# ngoc_say.net
KiCad netlist of a schematic drawn in Altium Designer
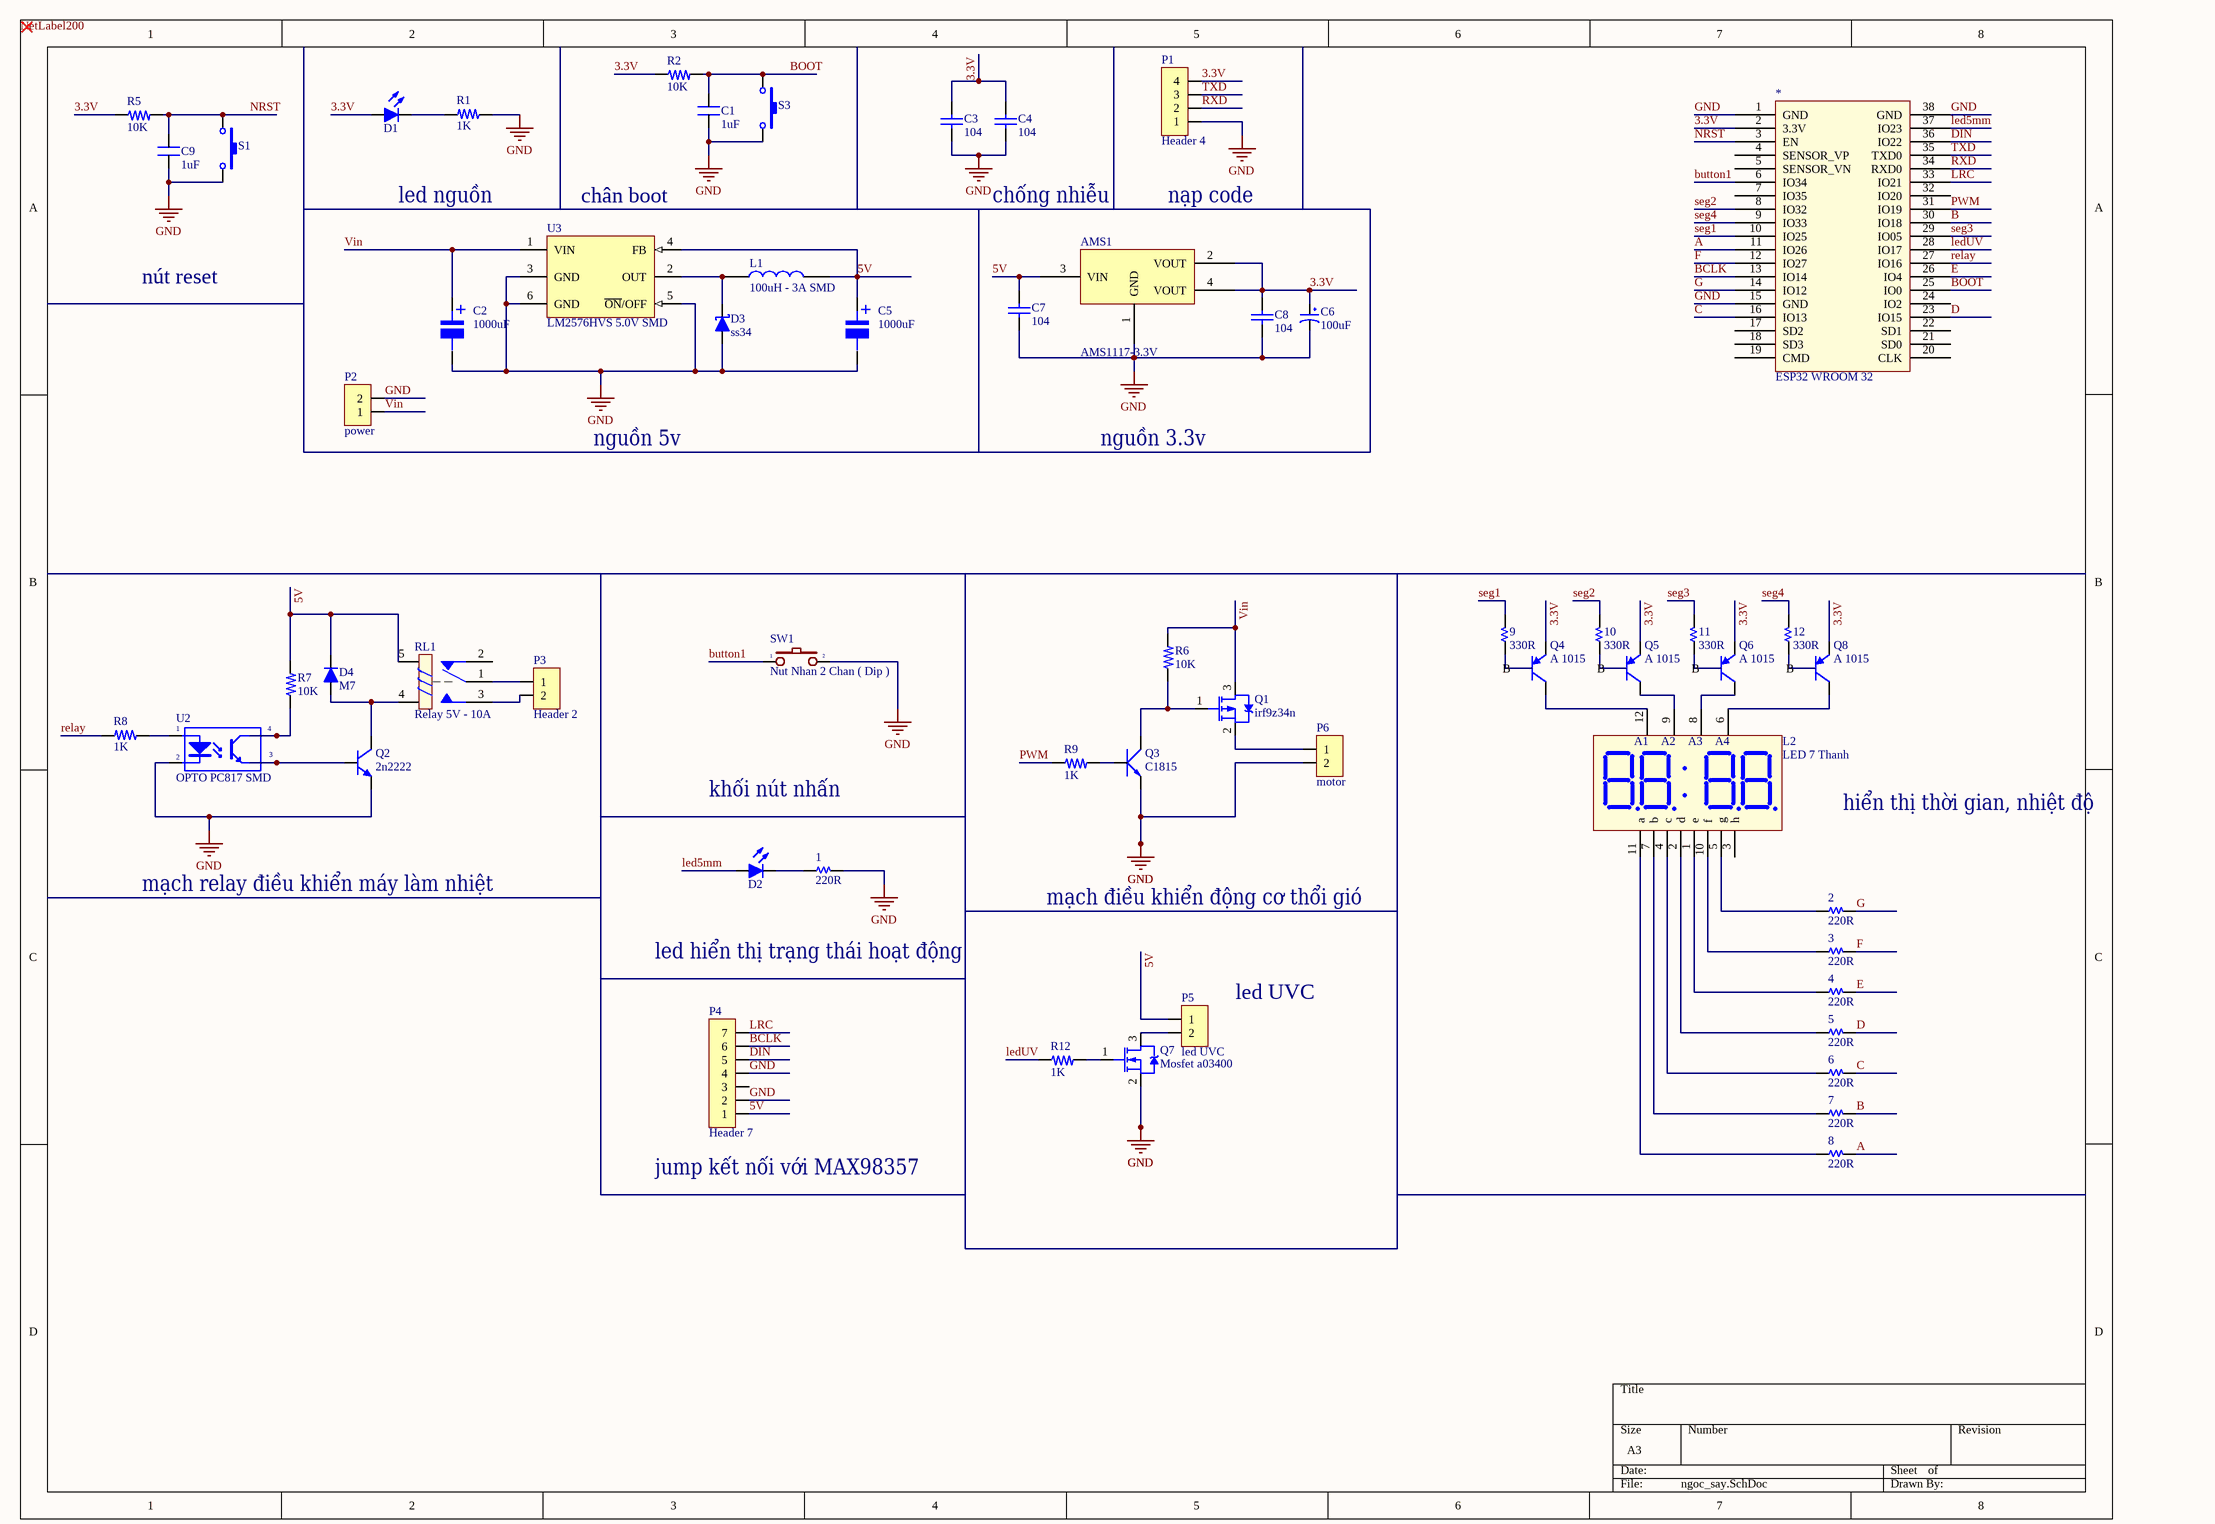
[diagram p0: ngoc_say.SchDoc]

(export (version "E")
  (design (tool "Eeschema 10.0.6"))
  (components
    (comp (ref "*")
      (value "ESP32 WROOM 32")
      (footprint "ESP32-WROOM-32")
      (libsource (lib "IC") (part "ESP32 WROOM 32"))
    )
    (comp (ref "1")
      (value "220R")
      (footprint "R 0805")
      (description "Resistor")
      (libsource (lib "chipfc_libs") (part "Resistor"))
    )
    (comp (ref "2")
      (value "220R")
      (footprint "R 0805")
      (description "Resistor")
      (libsource (lib "chipfc_libs") (part "Resistor"))
    )
    (comp (ref "3")
      (value "220R")
      (footprint "R 0805")
      (description "Resistor")
      (libsource (lib "chipfc_libs") (part "Resistor"))
    )
    (comp (ref "4")
      (value "220R")
      (footprint "R 0805")
      (description "Resistor")
      (libsource (lib "chipfc_libs") (part "Resistor"))
    )
    (comp (ref "5")
      (value "220R")
      (footprint "R 0805")
      (description "Resistor")
      (libsource (lib "chipfc_libs") (part "Resistor"))
    )
    (comp (ref "6")
      (value "220R")
      (footprint "R 0805")
      (description "Resistor")
      (libsource (lib "chipfc_libs") (part "Resistor"))
    )
    (comp (ref "7")
      (value "220R")
      (footprint "R 0805")
      (description "Resistor")
      (libsource (lib "chipfc_libs") (part "Resistor"))
    )
    (comp (ref "8")
      (value "220R")
      (footprint "R 0805")
      (description "Resistor")
      (libsource (lib "chipfc_libs") (part "Resistor"))
    )
    (comp (ref "9")
      (value "330R")
      (footprint "R 0805")
      (description "Resistor")
      (libsource (lib "chipfc_libs") (part "Resistor"))
    )
    (comp (ref "10")
      (value "330R")
      (footprint "R 0805")
      (description "Resistor")
      (libsource (lib "chipfc_libs") (part "Resistor"))
    )
    (comp (ref "11")
      (value "330R")
      (footprint "R 0805")
      (description "Resistor")
      (libsource (lib "chipfc_libs") (part "Resistor"))
    )
    (comp (ref "12")
      (value "330R")
      (footprint "R 0805")
      (description "Resistor")
      (libsource (lib "chipfc_libs") (part "Resistor"))
    )
    (comp (ref "AMS1")
      (value "AMS1117-3.3V")
      (footprint "SOT223")
      (description "Dán")
      (libsource (lib "IC") (part "AMS1117 SMD"))
    )
    (comp (ref "C1")
      (value "1uF")
      (footprint "CAP_0805")
      (description "1µF ±5% 50V Ceramic Capacitor X7R 0805 (2012 Metric)")
      (fields
        (field (name "MANUFACTURER") "Yageo")
        (field (name "MANUFACTURING PART NUMBER") "CC0805JKX7R9BB105")
      )
      (libsource (lib "STM_SCH_LIB") (part "CAP_1uF-50V-5%-0805"))
    )
    (comp (ref "C2")
      (value "1000uF")
      (footprint "tu nhom 10 (G)")
      (description "Dán")
      (libsource (lib "THU VIEN SCH") (part "Tu Nhom 1000uF 16V"))
    )
    (comp (ref "C3")
      (value "104")
      (footprint "Tu 0805")
      (description "Dán")
      (libsource (lib "THU VIEN SCH") (part "Tu 104"))
    )
    (comp (ref "C4")
      (value "104")
      (footprint "Tu 0805")
      (description "Dán")
      (libsource (lib "THU VIEN SCH") (part "Tu 104"))
    )
    (comp (ref "C5")
      (value "1000uF")
      (footprint "tu nhom 10 (G)")
      (description "Dán")
      (libsource (lib "THU VIEN SCH") (part "Tu Nhom 1000uF 16V"))
    )
    (comp (ref "C6")
      (value "100uF")
      (footprint "tu tantalum smd3528")
      (description "Dán")
      (libsource (lib "THU VIEN SCH") (part "Tu tantalum 100uF 6.3V SMD3528"))
    )
    (comp (ref "C7")
      (value "104")
      (footprint "Tu 0805")
      (description "Dán")
      (libsource (lib "THU VIEN SCH") (part "Tu 104"))
    )
    (comp (ref "C8")
      (value "104")
      (footprint "Tu 0805")
      (description "Dán")
      (libsource (lib "THU VIEN SCH") (part "Tu 104"))
    )
    (comp (ref "C9")
      (value "1uF")
      (footprint "CAP_0805")
      (description "1µF ±5% 50V Ceramic Capacitor X7R 0805 (2012 Metric)")
      (fields
        (field (name "MANUFACTURER") "Yageo")
        (field (name "MANUFACTURING PART NUMBER") "CC0805JKX7R9BB105")
      )
      (libsource (lib "STM_SCH_LIB") (part "CAP_1uF-50V-5%-0805"))
    )
    (comp (ref "D1")
      (value "Led")
      (footprint "Led 0805 RED")
      (description "Typical LED")
      (libsource (lib "led") (part "Led"))
    )
    (comp (ref "D2")
      (value "Led")
      (footprint "LED 5MM - RED")
      (description "Typical LED")
      (libsource (lib "led") (part "Led"))
    )
    (comp (ref "D3")
      (value "ss34")
      (footprint "SOD123")
      (description "Schottky Diode")
      (libsource (lib "chipfc_libs") (part "Diode Schottky"))
    )
    (comp (ref "D4")
      (value "M7")
      (footprint "DO-214AC (SMA) L")
      (description "Default Diode")
      (libsource (lib "chipfc_libs") (part "Diode"))
    )
    (comp (ref "L1")
      (value "100uH - 3A SMD")
      (footprint "Cuon Cam 7.5x7x5")
      (description "Dán")
      (libsource (lib "THU VIEN SCH") (part "CUON CAM 100uH_SMD"))
    )
    (comp (ref "L2")
      (value "LED 7 Thanh")
      (footprint "LED 7x4 0.36")
      (description "Dán")
      (libsource (lib "Led") (part "LED 7x4 0.36 Anot"))
    )
    (comp (ref "P1")
      (value "Header 4")
      (footprint "HDR/Header/4/2mm")
      (description "Header, 4-Pin")
      (libsource (lib "connectors") (part "Header 4"))
    )
    (comp (ref "P2")
      (value "power")
      (footprint "HDR/Header/2/BOX")
      (description "Header, 2-Pin")
      (libsource (lib "connectors") (part "Header 2"))
    )
    (comp (ref "P3")
      (value "Header 2")
      (footprint "HDR/Terminal/2")
      (description "Header, 2-Pin")
      (libsource (lib "") (part "Header 2_1"))
    )
    (comp (ref "P4")
      (value "Header 7")
      (footprint "HDR/Header/7/2mm")
      (description "Header, 7-Pin")
      (libsource (lib "connectors") (part "Header 7"))
    )
    (comp (ref "P5")
      (value "led UVC")
      (footprint "HDR/Header/2/BOX")
      (description "Header, 2-Pin")
      (libsource (lib "") (part "Header 2_1"))
    )
    (comp (ref "P6")
      (value "motor")
      (footprint "HDR/Header/2/BOX")
      (description "Header, 2-Pin")
      (libsource (lib "") (part "Header 2_1"))
    )
    (comp (ref "Q1")
      (value "irf9z34n")
      (footprint "TO-220/HeatSink")
      (description "Mosfet P")
      (libsource (lib "chipfc_libs") (part "Mosfet P"))
    )
    (comp (ref "Q2")
      (value "2n2222")
      (footprint "SOT-23")
      (description "NPN Bipolar Transistor")
      (libsource (lib "chipfc_libs") (part "Transistor NPN"))
    )
    (comp (ref "Q3")
      (value "C1815")
      (footprint "SOT23B")
      (description "Dán")
      (libsource (lib "THU VIEN SCH") (part "C1815"))
    )
    (comp (ref "Q4")
      (value "A 1015")
      (footprint "SOT23")
      (description "Dán")
      (libsource (lib "THU VIEN SCH") (part "2SA1015"))
    )
    (comp (ref "Q5")
      (value "A 1015")
      (footprint "SOT23")
      (description "Dán")
      (libsource (lib "THU VIEN SCH") (part "2SA1015"))
    )
    (comp (ref "Q6")
      (value "A 1015")
      (footprint "SOT23")
      (description "Dán")
      (libsource (lib "THU VIEN SCH") (part "2SA1015"))
    )
    (comp (ref "Q7")
      (value "Mosfet a03400")
      (footprint "SOT-23")
      (description "Mosfet N")
      (libsource (lib "chipfc_libs") (part "Mosfet N"))
    )
    (comp (ref "Q8")
      (value "A 1015")
      (footprint "SOT23")
      (description "Dán")
      (libsource (lib "THU VIEN SCH") (part "2SA1015"))
    )
    (comp (ref "R1")
      (value "1K")
      (footprint "RES_0805")
      (description "1 kOhms ±1% 0.125W, 1/8W Chip Resistor 0805 (2012 Metric) Moisture Resistant Thick Film")
      (fields (field (name "MANUFACTURER") "垈㎵á") (field (name "MANUFACTURER PART NUMBER") "RC0805FR-071KL"))
      (libsource (lib "STM_SCH_LIB") (part "RES_1K-0.125W-1%-0805"))
    )
    (comp (ref "R2")
      (value "10K")
      (footprint "RES_0805")
      (description "10 kOhms ±1% 0.125W, 1/8W Chip Resistor 0805 (2012 Metric) Moisture Resistant Thick Film")
      (fields
        (field (name "MANUFACTURER") "Yageo")
        (field (name "MANUFACTURING PART NUMBER") "RC0805FR-0710KL")
      )
      (libsource (lib "STM_SCH_LIB") (part "RES_10K-0.125W-1%-0805"))
    )
    (comp (ref "R5")
      (value "10K")
      (footprint "RES_0805")
      (description "10 kOhms ±1% 0.125W, 1/8W Chip Resistor 0805 (2012 Metric) Moisture Resistant Thick Film")
      (fields
        (field (name "MANUFACTURER") "Yageo")
        (field (name "MANUFACTURING PART NUMBER") "RC0805FR-0710KL")
      )
      (libsource (lib "STM_SCH_LIB") (part "RES_10K-0.125W-1%-0805"))
    )
    (comp (ref "R6")
      (value "10K")
      (footprint "RES_0805")
      (description "10 kOhms ±1% 0.125W, 1/8W Chip Resistor 0805 (2012 Metric) Moisture Resistant Thick Film")
      (fields
        (field (name "MANUFACTURER") "Yageo")
        (field (name "MANUFACTURING PART NUMBER") "RC0805FR-0710KL")
      )
      (libsource (lib "STM_SCH_LIB") (part "RES_10K-0.125W-1%-0805"))
    )
    (comp (ref "R7")
      (value "10K")
      (footprint "RES_0805")
      (description "10 kOhms ±1% 0.125W, 1/8W Chip Resistor 0805 (2012 Metric) Moisture Resistant Thick Film")
      (fields
        (field (name "MANUFACTURER") "Yageo")
        (field (name "MANUFACTURING PART NUMBER") "RC0805FR-0710KL")
      )
      (libsource (lib "STM_SCH_LIB") (part "RES_10K-0.125W-1%-0805"))
    )
    (comp (ref "R8")
      (value "1K")
      (footprint "RES_0805")
      (description "1 kOhms ±1% 0.125W, 1/8W Chip Resistor 0805 (2012 Metric) Moisture Resistant Thick Film")
      (fields (field (name "MANUFACTURER") "垈㎵á") (field (name "MANUFACTURER PART NUMBER") "RC0805FR-071KL"))
      (libsource (lib "STM_SCH_LIB") (part "RES_1K-0.125W-1%-0805"))
    )
    (comp (ref "R9")
      (value "1K")
      (footprint "RES_0805")
      (description "1 kOhms ±1% 0.125W, 1/8W Chip Resistor 0805 (2012 Metric) Moisture Resistant Thick Film")
      (fields (field (name "MANUFACTURER") "垈㎵á") (field (name "MANUFACTURER PART NUMBER") "RC0805FR-071KL"))
      (libsource (lib "STM_SCH_LIB") (part "RES_1K-0.125W-1%-0805"))
    )
    (comp (ref "R12")
      (value "1K")
      (footprint "RES_0805")
      (description "1 kOhms ±1% 0.125W, 1/8W Chip Resistor 0805 (2012 Metric) Moisture Resistant Thick Film")
      (fields (field (name "MANUFACTURER") "垈㎵á") (field (name "MANUFACTURER PART NUMBER") "RC0805FR-071KL"))
      (libsource (lib "STM_SCH_LIB") (part "RES_1K-0.125W-1%-0805"))
    )
    (comp (ref "RL1")
      (value "Relay 5V - 10A")
      (footprint "RELAY5PIN-10A")
      (description "Cắm")
      (fields (field (name "Comment") "MH"))
      (libsource (lib "THU VIEN SCH") (part "Relay 10A"))
    )
    (comp (ref "S1")
      (value "MH001036")
      (footprint "SW-SMD")
      (description "Dán")
      (libsource (lib "THU VIEN SCH") (part "SW-SMD"))
    )
    (comp (ref "S3")
      (value "MH001036")
      (footprint "SW-SMD")
      (description "Dán")
      (libsource (lib "THU VIEN SCH") (part "SW-SMD"))
    )
    (comp (ref "SW1")
      (value "Nut Nhan 2 Chan ( Dip )")
      (footprint "SW2")
      (description "Cắm")
      (libsource (lib "THU VIEN SCH") (part "Nut Nhan 2 Chan ( Dip )"))
    )
    (comp (ref "U2")
      (value "OPTO PC817 SMD")
      (footprint "SOP4")
      (description "Single Opto")
      (libsource (lib "IC") (part "OPTO PC817 SMD"))
    )
    (comp (ref "U3")
      (value "LM2576HVS 5.0V SMD")
      (footprint "TO263-5")
      (description "Dán")
      (libsource (lib "IC") (part "LM2576HVS 5.0V SMD"))
    )
  )
  (nets
    (net (code "1") (name "/3.3V") (class "Default")
      (node (ref "*") (pin "2") (pinfunction "3.3V_2") (pintype "passive"))
      (node (ref "AMS1") (pin "2") (pinfunction "VOUT_2") (pintype "passive"))
      (node (ref "AMS1") (pin "4") (pinfunction "VOUT_4") (pintype "passive"))
      (node (ref "C3") (pin "2") (pinfunction "2_2") (pintype "passive"))
      (node (ref "C4") (pin "2") (pinfunction "2_2") (pintype "passive"))
      (node (ref "C6") (pin "1") (pinfunction "1_1") (pintype "passive"))
      (node (ref "C8") (pin "2") (pinfunction "2_2") (pintype "passive"))
      (node (ref "D1") (pin "1") (pinfunction "A_1") (pintype "passive"))
      (node (ref "P1") (pin "4") (pinfunction "4_4") (pintype "passive"))
      (node (ref "Q4") (pin "3") (pinfunction "E_3") (pintype "passive"))
      (node (ref "Q5") (pin "3") (pinfunction "E_3") (pintype "passive"))
      (node (ref "Q6") (pin "3") (pinfunction "E_3") (pintype "passive"))
      (node (ref "Q8") (pin "3") (pinfunction "E_3") (pintype "passive"))
      (node (ref "R2") (pin "2") (pinfunction "2_2") (pintype "passive"))
      (node (ref "R5") (pin "2") (pinfunction "2_2") (pintype "passive"))
    )
    (net (code "2") (name "/5V") (class "Default")
      (node (ref "AMS1") (pin "3") (pinfunction "VIN_3") (pintype "passive"))
      (node (ref "C5") (pin "1") (pinfunction "1_1") (pintype "passive"))
      (node (ref "C7") (pin "2") (pinfunction "2_2") (pintype "passive"))
      (node (ref "D4") (pin "2") (pinfunction "K_2") (pintype "passive"))
      (node (ref "L1") (pin "2") (pinfunction "2_2") (pintype "passive"))
      (node (ref "P4") (pin "1") (pinfunction "1_1") (pintype "passive"))
      (node (ref "P5") (pin "1") (pinfunction "1_1") (pintype "passive"))
      (node (ref "R7") (pin "1") (pinfunction "1_1") (pintype "passive"))
      (node (ref "RL1") (pin "5") (pinfunction "5_5") (pintype "passive"))
      (node (ref "U3") (pin "4") (pinfunction "FB_4") (pintype "input"))
    )
    (net (code "3") (name "/A") (class "Default")
      (node (ref "*") (pin "11") (pinfunction "IO26_11") (pintype "passive"))
      (node (ref "8") (pin "2") (pinfunction "2_2") (pintype "passive"))
    )
    (net (code "4") (name "/B") (class "Default")
      (node (ref "*") (pin "30") (pinfunction "IO18_30") (pintype "passive"))
      (node (ref "7") (pin "2") (pinfunction "2_2") (pintype "passive"))
    )
    (net (code "5") (name "/BCLK") (class "Default")
      (node (ref "*") (pin "13") (pinfunction "IO14_13") (pintype "passive"))
      (node (ref "P4") (pin "6") (pinfunction "6_6") (pintype "passive"))
    )
    (net (code "6") (name "/BOOT") (class "Default")
      (node (ref "*") (pin "25") (pinfunction "IO0_25") (pintype "passive"))
      (node (ref "C1") (pin "2") (pinfunction "2_2") (pintype "passive"))
      (node (ref "R2") (pin "1") (pinfunction "1_1") (pintype "passive"))
      (node (ref "S3") (pin "1") (pinfunction "1_1") (pintype "passive"))
    )
    (net (code "7") (name "/C") (class "Default")
      (node (ref "*") (pin "16") (pinfunction "IO13_16") (pintype "passive"))
      (node (ref "6") (pin "2") (pinfunction "2_2") (pintype "passive"))
    )
    (net (code "8") (name "/D") (class "Default")
      (node (ref "*") (pin "23") (pinfunction "IO15_23") (pintype "passive"))
      (node (ref "5") (pin "2") (pinfunction "2_2") (pintype "passive"))
    )
    (net (code "9") (name "/DIN") (class "Default")
      (node (ref "*") (pin "36") (pinfunction "IO22_36") (pintype "passive"))
      (node (ref "P4") (pin "5") (pinfunction "5_5") (pintype "passive"))
    )
    (net (code "10") (name "/E") (class "Default")
      (node (ref "*") (pin "26") (pinfunction "IO4_26") (pintype "passive"))
      (node (ref "4") (pin "2") (pinfunction "2_2") (pintype "passive"))
    )
    (net (code "11") (name "/F") (class "Default")
      (node (ref "*") (pin "12") (pinfunction "IO27_12") (pintype "passive"))
      (node (ref "3") (pin "2") (pinfunction "2_2") (pintype "passive"))
    )
    (net (code "12") (name "/G") (class "Default")
      (node (ref "*") (pin "14") (pinfunction "IO12_14") (pintype "passive"))
      (node (ref "2") (pin "2") (pinfunction "2_2") (pintype "passive"))
    )
    (net (code "13") (name "/LRC") (class "Default")
      (node (ref "*") (pin "33") (pinfunction "IO21_33") (pintype "passive"))
      (node (ref "P4") (pin "7") (pinfunction "7_7") (pintype "passive"))
    )
    (net (code "14") (name "/NRST") (class "Default")
      (node (ref "*") (pin "3") (pinfunction "EN_3") (pintype "passive"))
      (node (ref "C9") (pin "2") (pinfunction "2_2") (pintype "passive"))
      (node (ref "R5") (pin "1") (pinfunction "1_1") (pintype "passive"))
      (node (ref "S1") (pin "1") (pinfunction "1_1") (pintype "passive"))
    )
    (net (code "16") (name "/PWM") (class "Default")
      (node (ref "*") (pin "31") (pinfunction "IO19_31") (pintype "passive"))
      (node (ref "R9") (pin "2") (pinfunction "2_2") (pintype "passive"))
    )
    (net (code "17") (name "/RXD") (class "Default")
      (node (ref "*") (pin "34") (pinfunction "RXD0_34") (pintype "passive"))
      (node (ref "P1") (pin "2") (pinfunction "2_2") (pintype "passive"))
    )
    (net (code "18") (name "/TXD") (class "Default")
      (node (ref "*") (pin "35") (pinfunction "TXD0_35") (pintype "passive"))
      (node (ref "P1") (pin "3") (pinfunction "3_3") (pintype "passive"))
    )
    (net (code "19") (name "/Vin") (class "Default")
      (node (ref "C2") (pin "1") (pinfunction "1_1") (pintype "passive"))
      (node (ref "P2") (pin "1") (pinfunction "1_1") (pintype "passive"))
      (node (ref "Q1") (pin "3") (pinfunction "D_3") (pintype "passive"))
      (node (ref "R6") (pin "1") (pinfunction "1_1") (pintype "passive"))
      (node (ref "U3") (pin "1") (pinfunction "VIN_1") (pintype "power_in"))
    )
    (net (code "20") (name "/button1") (class "Default")
      (node (ref "*") (pin "6") (pinfunction "IO34_6") (pintype "passive"))
      (node (ref "SW1") (pin "1") (pinfunction "1_1") (pintype "passive"))
    )
    (net (code "21") (name "/led5mm") (class "Default")
      (node (ref "*") (pin "37") (pinfunction "IO23_37") (pintype "passive"))
      (node (ref "D2") (pin "1") (pinfunction "A_1") (pintype "passive"))
    )
    (net (code "22") (name "/ledUV") (class "Default")
      (node (ref "*") (pin "28") (pinfunction "IO17_28") (pintype "passive"))
      (node (ref "R12") (pin "2") (pinfunction "2_2") (pintype "passive"))
    )
    (net (code "23") (name "/relay") (class "Default")
      (node (ref "*") (pin "27") (pinfunction "IO16_27") (pintype "passive"))
      (node (ref "R8") (pin "1") (pinfunction "1_1") (pintype "passive"))
    )
    (net (code "24") (name "/seg1") (class "Default")
      (node (ref "*") (pin "10") (pinfunction "IO25_10") (pintype "passive"))
      (node (ref "9") (pin "2") (pinfunction "2_2") (pintype "passive"))
    )
    (net (code "25") (name "/seg2") (class "Default")
      (node (ref "*") (pin "8") (pinfunction "IO32_8") (pintype "passive"))
      (node (ref "10") (pin "2") (pinfunction "2_2") (pintype "passive"))
    )
    (net (code "26") (name "/seg3") (class "Default")
      (node (ref "*") (pin "29") (pinfunction "IO05_29") (pintype "passive"))
      (node (ref "11") (pin "2") (pinfunction "2_2") (pintype "passive"))
    )
    (net (code "27") (name "/seg4") (class "Default")
      (node (ref "*") (pin "9") (pinfunction "IO33_9") (pintype "passive"))
      (node (ref "12") (pin "2") (pinfunction "2_2") (pintype "passive"))
    )
    (net (code "28") (name "GND") (class "Default")
      (node (ref "*") (pin "1") (pinfunction "GND_1") (pintype "passive"))
      (node (ref "*") (pin "15") (pinfunction "GND_15") (pintype "passive"))
      (node (ref "*") (pin "38") (pinfunction "GND_38") (pintype "passive"))
      (node (ref "1") (pin "2") (pinfunction "2_2") (pintype "passive"))
      (node (ref "AMS1") (pin "1") (pinfunction "GND_1") (pintype "passive"))
      (node (ref "C1") (pin "1") (pinfunction "1_1") (pintype "passive"))
      (node (ref "C2") (pin "2") (pinfunction "2_2") (pintype "passive"))
      (node (ref "C3") (pin "1") (pinfunction "1_1") (pintype "passive"))
      (node (ref "C4") (pin "1") (pinfunction "1_1") (pintype "passive"))
      (node (ref "C5") (pin "2") (pinfunction "2_2") (pintype "passive"))
      (node (ref "C6") (pin "2") (pinfunction "2_2") (pintype "passive"))
      (node (ref "C7") (pin "1") (pinfunction "1_1") (pintype "passive"))
      (node (ref "C8") (pin "1") (pinfunction "1_1") (pintype "passive"))
      (node (ref "C9") (pin "1") (pinfunction "1_1") (pintype "passive"))
      (node (ref "D3") (pin "1") (pinfunction "A_1") (pintype "passive"))
      (node (ref "P1") (pin "1") (pinfunction "1_1") (pintype "passive"))
      (node (ref "P2") (pin "2") (pinfunction "2_2") (pintype "passive"))
      (node (ref "P4") (pin "2") (pinfunction "2_2") (pintype "passive"))
      (node (ref "P4") (pin "4") (pinfunction "4_4") (pintype "passive"))
      (node (ref "P6") (pin "2") (pinfunction "2_2") (pintype "passive"))
      (node (ref "Q2") (pin "2") (pinfunction "E_2") (pintype "passive"))
      (node (ref "Q3") (pin "3") (pinfunction "E_3") (pintype "passive"))
      (node (ref "Q7") (pin "2") (pinfunction "S_2") (pintype "passive"))
      (node (ref "R1") (pin "2") (pinfunction "2_2") (pintype "passive"))
      (node (ref "S1") (pin "2") (pinfunction "2_2") (pintype "passive"))
      (node (ref "S3") (pin "2") (pinfunction "2_2") (pintype "passive"))
      (node (ref "SW1") (pin "2") (pinfunction "2_2") (pintype "passive"))
      (node (ref "U2") (pin "2") (pinfunction "K_2") (pintype "passive"))
      (node (ref "U3") (pin "3") (pinfunction "GND_3") (pintype "power_in"))
      (node (ref "U3") (pin "5") (pinfunction "~{ON}/OFF_5") (pintype "input"))
      (node (ref "U3") (pin "6") (pinfunction "GND_6") (pintype "passive"))
    )
    (net (code "29") (name "Net-(D1-K)") (class "Default")
      (node (ref "D1") (pin "2") (pinfunction "K_2") (pintype "passive"))
      (node (ref "R1") (pin "1") (pinfunction "1_1") (pintype "passive"))
    )
    (net (code "30") (name "Net-(D2-K)") (class "Default")
      (node (ref "1") (pin "1") (pinfunction "1_1") (pintype "passive"))
      (node (ref "D2") (pin "2") (pinfunction "K_2") (pintype "passive"))
    )
    (net (code "31") (name "Net-(D3-K)") (class "Default")
      (node (ref "D3") (pin "2") (pinfunction "K_2") (pintype "passive"))
      (node (ref "L1") (pin "1") (pinfunction "1_1") (pintype "passive"))
      (node (ref "U3") (pin "2") (pinfunction "OUT_2") (pintype "power_in"))
    )
    (net (code "32") (name "Net-(D4-A)") (class "Default")
      (node (ref "D4") (pin "1") (pinfunction "A_1") (pintype "passive"))
      (node (ref "Q2") (pin "3") (pinfunction "C_3") (pintype "passive"))
      (node (ref "RL1") (pin "4") (pinfunction "4_4") (pintype "passive"))
    )
    (net (code "33") (name "Net-(L2-V1)") (class "Default")
      (node (ref "L2") (pin "12") (pinfunction "V1_12") (pintype "passive"))
      (node (ref "Q4") (pin "2") (pinfunction "C_2") (pintype "passive"))
    )
    (net (code "34") (name "Net-(L2-V2)") (class "Default")
      (node (ref "L2") (pin "9") (pinfunction "V2_9") (pintype "passive"))
      (node (ref "Q5") (pin "2") (pinfunction "C_2") (pintype "passive"))
    )
    (net (code "35") (name "Net-(L2-V3)") (class "Default")
      (node (ref "L2") (pin "8") (pinfunction "V3_8") (pintype "passive"))
      (node (ref "Q6") (pin "2") (pinfunction "C_2") (pintype "passive"))
    )
    (net (code "36") (name "Net-(L2-V4)") (class "Default")
      (node (ref "L2") (pin "6") (pinfunction "V4_6") (pintype "passive"))
      (node (ref "Q8") (pin "2") (pinfunction "C_2") (pintype "passive"))
    )
    (net (code "37") (name "Net-(L2-a)") (class "Default")
      (node (ref "8") (pin "1") (pinfunction "1_1") (pintype "passive"))
      (node (ref "L2") (pin "11") (pinfunction "a_11") (pintype "passive"))
    )
    (net (code "38") (name "Net-(L2-b)") (class "Default")
      (node (ref "7") (pin "1") (pinfunction "1_1") (pintype "passive"))
      (node (ref "L2") (pin "7") (pinfunction "b_7") (pintype "passive"))
    )
    (net (code "39") (name "Net-(L2-c)") (class "Default")
      (node (ref "6") (pin "1") (pinfunction "1_1") (pintype "passive"))
      (node (ref "L2") (pin "4") (pinfunction "c_4") (pintype "passive"))
    )
    (net (code "40") (name "Net-(L2-d)") (class "Default")
      (node (ref "5") (pin "1") (pinfunction "1_1") (pintype "passive"))
      (node (ref "L2") (pin "2") (pinfunction "d_2") (pintype "passive"))
    )
    (net (code "41") (name "Net-(L2-e)") (class "Default")
      (node (ref "4") (pin "1") (pinfunction "1_1") (pintype "passive"))
      (node (ref "L2") (pin "1") (pinfunction "e_1") (pintype "passive"))
    )
    (net (code "42") (name "Net-(L2-f)") (class "Default")
      (node (ref "3") (pin "1") (pinfunction "1_1") (pintype "passive"))
      (node (ref "L2") (pin "10") (pinfunction "f_10") (pintype "passive"))
    )
    (net (code "43") (name "Net-(L2-g)") (class "Default")
      (node (ref "2") (pin "1") (pinfunction "1_1") (pintype "passive"))
      (node (ref "L2") (pin "5") (pinfunction "g_5") (pintype "passive"))
    )
    (net (code "44") (name "Net-(P3-Pad1)") (class "Default")
      (node (ref "P3") (pin "1") (pinfunction "1_1") (pintype "passive"))
      (node (ref "RL1") (pin "1") (pinfunction "1_1") (pintype "passive"))
    )
    (net (code "45") (name "Net-(P3-Pad2)") (class "Default")
      (node (ref "P3") (pin "2") (pinfunction "2_2") (pintype "passive"))
      (node (ref "RL1") (pin "3") (pinfunction "3_3") (pintype "passive"))
    )
    (net (code "46") (name "Net-(Q1-G)") (class "Default")
      (node (ref "Q1") (pin "1") (pinfunction "G_1") (pintype "passive"))
      (node (ref "Q3") (pin "2") (pinfunction "C_2") (pintype "passive"))
      (node (ref "R6") (pin "2") (pinfunction "2_2") (pintype "passive"))
    )
    (net (code "47") (name "Net-(Q1-S)") (class "Default")
      (node (ref "P6") (pin "1") (pinfunction "1_1") (pintype "passive"))
      (node (ref "Q1") (pin "2") (pinfunction "S_2") (pintype "passive"))
    )
    (net (code "48") (name "Net-(Q2-B)") (class "Default")
      (node (ref "Q2") (pin "1") (pinfunction "B_1") (pintype "passive"))
      (node (ref "U2") (pin "3") (pinfunction "E_3") (pintype "passive"))
    )
    (net (code "49") (name "Net-(Q3-B)") (class "Default")
      (node (ref "Q3") (pin "1") (pinfunction "B_1") (pintype "passive"))
      (node (ref "R9") (pin "1") (pinfunction "1_1") (pintype "passive"))
    )
    (net (code "50") (name "Net-(Q4-B)") (class "Default")
      (node (ref "9") (pin "1") (pinfunction "1_1") (pintype "passive"))
      (node (ref "Q4") (pin "1") (pinfunction "B_1") (pintype "passive"))
    )
    (net (code "51") (name "Net-(Q5-B)") (class "Default")
      (node (ref "10") (pin "1") (pinfunction "1_1") (pintype "passive"))
      (node (ref "Q5") (pin "1") (pinfunction "B_1") (pintype "passive"))
    )
    (net (code "52") (name "Net-(Q6-B)") (class "Default")
      (node (ref "11") (pin "1") (pinfunction "1_1") (pintype "passive"))
      (node (ref "Q6") (pin "1") (pinfunction "B_1") (pintype "passive"))
    )
    (net (code "53") (name "Net-(Q7-D)") (class "Default")
      (node (ref "P5") (pin "2") (pinfunction "2_2") (pintype "passive"))
      (node (ref "Q7") (pin "3") (pinfunction "D_3") (pintype "passive"))
    )
    (net (code "54") (name "Net-(Q7-G)") (class "Default")
      (node (ref "Q7") (pin "1") (pinfunction "G_1") (pintype "passive"))
      (node (ref "R12") (pin "1") (pinfunction "1_1") (pintype "passive"))
    )
    (net (code "55") (name "Net-(Q8-B)") (class "Default")
      (node (ref "12") (pin "1") (pinfunction "1_1") (pintype "passive"))
      (node (ref "Q8") (pin "1") (pinfunction "B_1") (pintype "passive"))
    )
    (net (code "56") (name "Net-(U2-A)") (class "Default")
      (node (ref "R8") (pin "2") (pinfunction "2_2") (pintype "passive"))
      (node (ref "U2") (pin "1") (pinfunction "A_1") (pintype "passive"))
    )
    (net (code "57") (name "Net-(U2-C)") (class "Default")
      (node (ref "R7") (pin "2") (pinfunction "2_2") (pintype "passive"))
      (node (ref "U2") (pin "4") (pinfunction "C_4") (pintype "passive"))
    )
    (net (code "58") (name "unconnected-(*-CLK-Pad20)") (class "Default")
      (node (ref "*") (pin "20") (pinfunction "CLK_20") (pintype "passive"))
    )
    (net (code "59") (name "unconnected-(*-CMD-Pad19)") (class "Default")
      (node (ref "*") (pin "19") (pinfunction "CMD_19") (pintype "passive"))
    )
    (net (code "60") (name "unconnected-(*-IO2-Pad24)") (class "Default")
      (node (ref "*") (pin "24") (pinfunction "IO2_24") (pintype "passive"))
    )
    (net (code "61") (name "unconnected-(*-IO20-Pad32)") (class "Default")
      (node (ref "*") (pin "32") (pinfunction "IO20_32") (pintype "passive"))
    )
    (net (code "62") (name "unconnected-(*-IO35-Pad7)") (class "Default")
      (node (ref "*") (pin "7") (pinfunction "IO35_7") (pintype "passive"))
    )
    (net (code "63") (name "unconnected-(*-SD0-Pad21)") (class "Default")
      (node (ref "*") (pin "21") (pinfunction "SD0_21") (pintype "passive"))
    )
    (net (code "64") (name "unconnected-(*-SD1-Pad22)") (class "Default")
      (node (ref "*") (pin "22") (pinfunction "SD1_22") (pintype "passive"))
    )
    (net (code "65") (name "unconnected-(*-SD2-Pad17)") (class "Default")
      (node (ref "*") (pin "17") (pinfunction "SD2_17") (pintype "passive"))
    )
    (net (code "66") (name "unconnected-(*-SD3-Pad18)") (class "Default")
      (node (ref "*") (pin "18") (pinfunction "SD3_18") (pintype "passive"))
    )
    (net (code "67") (name "unconnected-(*-SENSOR_VN-Pad5)") (class "Default")
      (node (ref "*") (pin "5") (pinfunction "SENSOR_VN_5") (pintype "passive"))
    )
    (net (code "68") (name "unconnected-(*-SENSOR_VP-Pad4)") (class "Default")
      (node (ref "*") (pin "4") (pinfunction "SENSOR_VP_4") (pintype "passive"))
    )
    (net (code "69") (name "unconnected-(L2-h-Pad3)") (class "Default")
      (node (ref "L2") (pin "3") (pinfunction "h_3") (pintype "passive"))
    )
    (net (code "70") (name "unconnected-(P4-Pad3)") (class "Default")
      (node (ref "P4") (pin "3") (pinfunction "3_3") (pintype "passive"))
    )
    (net (code "71") (name "unconnected-(RL1-Pad2)") (class "Default")
      (node (ref "RL1") (pin "2") (pinfunction "2_2") (pintype "passive"))
    )
  )
)
